# ATSAMB11.net
KiCad netlist of a schematic drawn in Altium Designer
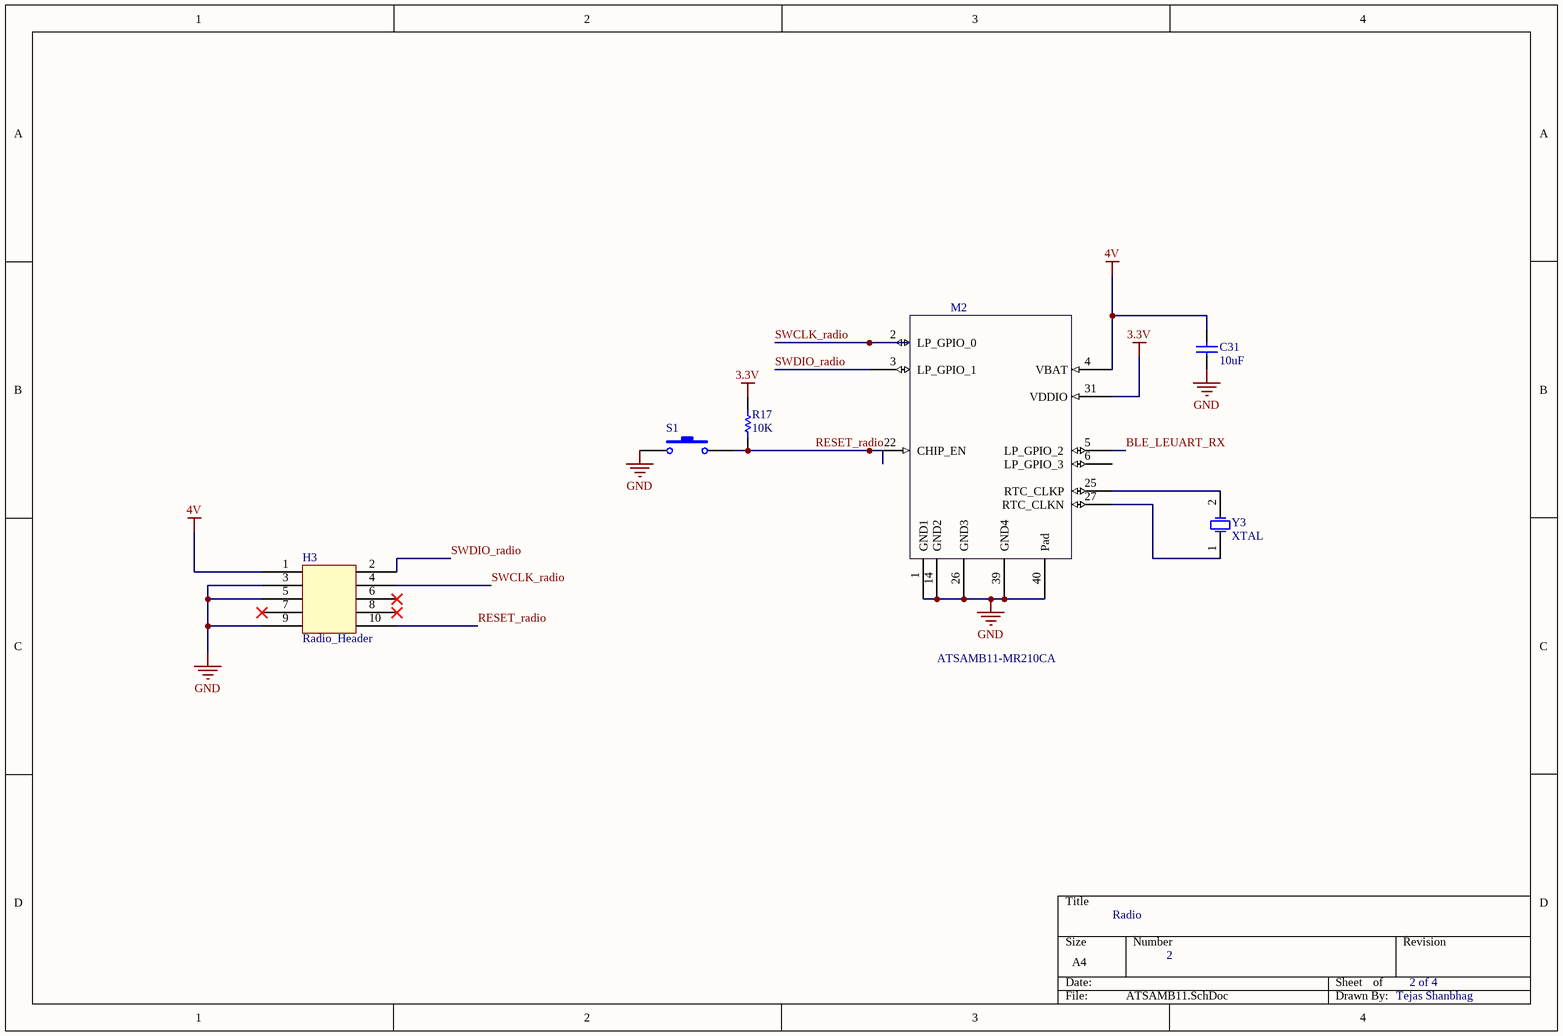
[diagram p0: ATSAMB11.SchDoc]

(export (version "E")
  (design (tool "Eeschema 10.0.6"))
  (components
    (comp (ref "C31")
      (value "10uF")
      (footprint "1608[0603]")
      (description "CAP CER 10UF 10V X5R 0603")
      (fields
        (field (name "DIGIKEY PART NO") "490-10474-1-ND")
        (field (name "MANUFACTURER") "Murata Electronics North America")
      )
      (libsource (lib "Miscellaneous Devices") (part "Cap Semi"))
    )
    (comp (ref "H3")
      (value "Radio_Header")
      (footprint "Cortex Debug Header")
      (description "CONN HDR 1.27MM SMD AU 10POS")
      (fields
        (field (name "MANUFACTURER") "Harwin Inc.")
        (field (name "MANUFACTURER PART NUMBER") "M50-3600542")
      )
      (libsource (lib "parts") (part "Radio_Header"))
    )
    (comp (ref "M2")
      (value "ATSAMB11-MR210CA")
      (footprint "ATMELSAMB11")
      (description "Bluetooth / 802.15.1 Modules Chip Antenna UFL connector MU-T")
      (fields
        (field (name "MANUFACTURER") "Microchip Technology/Atmel")
        (field (name "MOUSER PART NO") "556-ATSAMB11-MR210CA")
      )
      (libsource (lib "robo") (part "ATSAMB11"))
    )
    (comp (ref "R17")
      (value "10K")
      (footprint "1608[0603]")
      (description "RES SMD 10K OHM 1% 1/10W 0603")
      (fields (field (name "DIGIKEY PART NO") "311-10.0KHRCT-ND") (field (name "MANUFACTURER") "Yageo"))
      (libsource (lib "Miscellaneous Devices") (part "Res1"))
    )
    (comp (ref "S1")
      (value "SW-PB")
      (footprint "RESET")
      (description "SWITCH TACTILE SPST-NO 0.05A 15V")
      (fields
        (field (name "DIGIKEY PART NO") "EG4621CT-ND")
        (field (name "MANUFACTURER PART NUMBER") "TL3315NF160Q")
      )
      (libsource (lib "Parts") (part "SW-PB"))
    )
    (comp (ref "Y3")
      (value "XTAL")
      (footprint "Clock_LFXTAL")
      (description "CRYSTAL 32.7680KHZ 12.5PF SMD")
      (fields
        (field (name "MANUFACTURER PART NUMBER") "AB26TRQ-32.768KHZ-T")
        (field (name "DIGIKEY PART NO") "535-12051-1-ND")
      )
      (libsource (lib "Miscellaneous Devices") (part "XTAL"))
    )
  )
  (nets
    (net (code "1") (name "/BLE_LEUART_RX") (class "Default")
      (node (ref "M2") (pin "5") (pinfunction "LP_GPIO_2_5") (pintype "bidirectional"))
    )
    (net (code "2") (name "/RESET_radio") (class "Default")
      (node (ref "H3") (pin "10") (pinfunction "10_10") (pintype "passive"))
      (node (ref "M2") (pin "22") (pinfunction "CHIP_EN_22") (pintype "input"))
      (node (ref "R17") (pin "1") (pinfunction "1_1") (pintype "passive"))
      (node (ref "S1") (pin "2") (pinfunction "2_2") (pintype "passive"))
    )
    (net (code "3") (name "/SWCLK_radio") (class "Default")
      (node (ref "H3") (pin "4") (pinfunction "4_4") (pintype "passive"))
      (node (ref "M2") (pin "2") (pinfunction "LP_GPIO_0_2") (pintype "bidirectional"))
    )
    (net (code "4") (name "/SWDIO_radio") (class "Default")
      (node (ref "H3") (pin "2") (pinfunction "2_2") (pintype "passive"))
      (node (ref "M2") (pin "3") (pinfunction "LP_GPIO_1_3") (pintype "bidirectional"))
    )
    (net (code "5") (name "3.3V") (class "Default")
      (node (ref "M2") (pin "31") (pinfunction "VDDIO_31") (pintype "input"))
      (node (ref "R17") (pin "2") (pinfunction "2_2") (pintype "passive"))
    )
    (net (code "6") (name "4V") (class "Default")
      (node (ref "C31") (pin "2") (pinfunction "2_2") (pintype "passive"))
      (node (ref "H3") (pin "1") (pinfunction "1_1") (pintype "passive"))
      (node (ref "M2") (pin "4") (pinfunction "VBAT_4") (pintype "input"))
    )
    (net (code "7") (name "GND") (class "Default")
      (node (ref "C31") (pin "1") (pinfunction "1_1") (pintype "passive"))
      (node (ref "H3") (pin "3") (pinfunction "3_3") (pintype "passive"))
      (node (ref "H3") (pin "5") (pinfunction "5_5") (pintype "passive"))
      (node (ref "H3") (pin "9") (pinfunction "9_9") (pintype "passive"))
      (node (ref "M2") (pin "1") (pinfunction "GND1_1") (pintype "power_in"))
      (node (ref "M2") (pin "14") (pinfunction "GND2_14") (pintype "power_in"))
      (node (ref "M2") (pin "26") (pinfunction "GND3_26") (pintype "power_in"))
      (node (ref "M2") (pin "39") (pinfunction "GND4_39") (pintype "power_in"))
      (node (ref "M2") (pin "40") (pinfunction "Pad_40") (pintype "power_in"))
      (node (ref "S1") (pin "1") (pinfunction "1_1") (pintype "passive"))
    )
    (net (code "8") (name "Net-(M2-RTC_CLKN)") (class "Default")
      (node (ref "M2") (pin "27") (pinfunction "RTC_CLKN_27") (pintype "bidirectional"))
      (node (ref "Y3") (pin "1") (pinfunction "OSC1_1") (pintype "passive"))
    )
    (net (code "9") (name "Net-(M2-RTC_CLKP)") (class "Default")
      (node (ref "M2") (pin "25") (pinfunction "RTC_CLKP_25") (pintype "bidirectional"))
      (node (ref "Y3") (pin "2") (pinfunction "OSC2_2") (pintype "passive"))
    )
    (net (code "10") (name "unconnected-(H3-Pad6)") (class "Default")
      (node (ref "H3") (pin "6") (pinfunction "6_6") (pintype "passive+no_connect"))
    )
    (net (code "11") (name "unconnected-(H3-Pad7)") (class "Default")
      (node (ref "H3") (pin "7") (pinfunction "7_7") (pintype "passive+no_connect"))
    )
    (net (code "12") (name "unconnected-(H3-Pad8)") (class "Default")
      (node (ref "H3") (pin "8") (pinfunction "8_8") (pintype "passive+no_connect"))
    )
    (net (code "13") (name "unconnected-(M2-LP_GPIO_3-Pad6)") (class "Default")
      (node (ref "M2") (pin "6") (pinfunction "LP_GPIO_3_6") (pintype "bidirectional"))
    )
  )
)
